# PCB_ExpansionModule_EXISTING_ERRORS.net
KiCad netlist of a schematic drawn in EasyEDA Pro
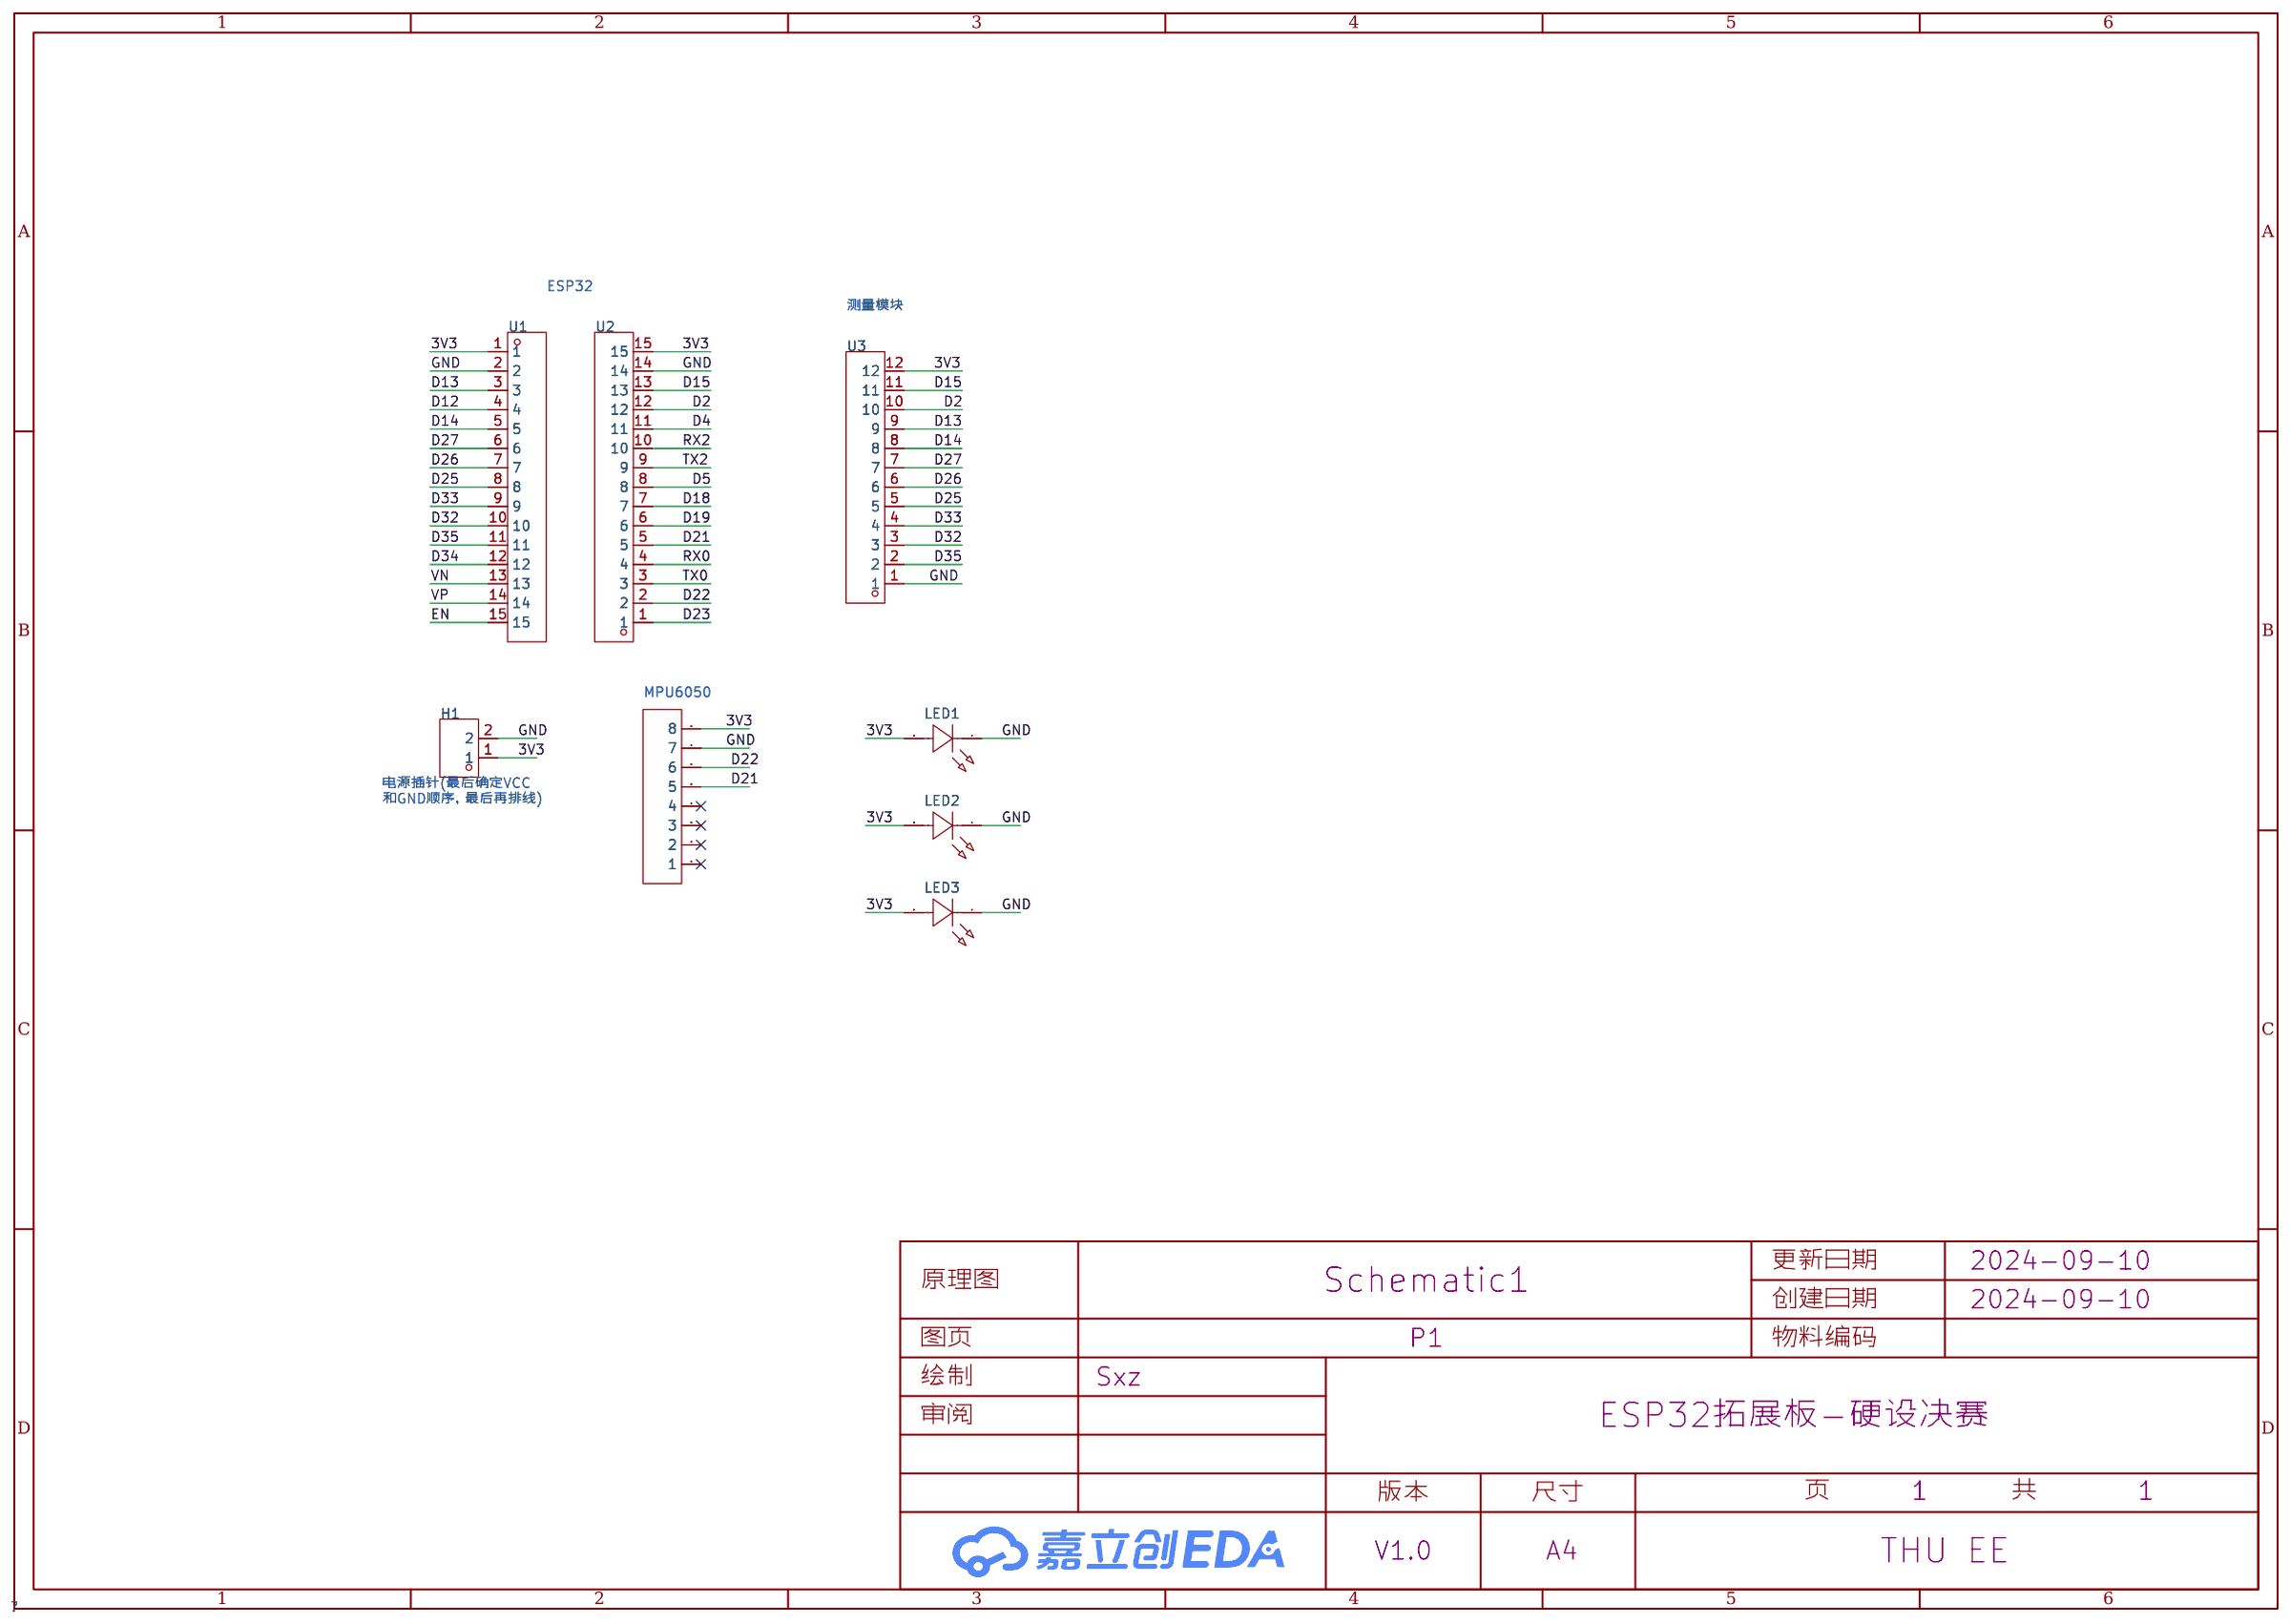
[diagram p0: schematic sheet]

(export (version "E")
  (design (tool "Eeschema 10.0.6"))
  (components
    (comp (ref "H1")
      (value "{制造商编号!}")
      (footprint "easyedapro:HDR-TH_2P-P2.54-H-M-W10.4")
      (fields (field (name "Manufacturer Part") "PZ254R-11-02P") (field (name "Manufacturer") "XFCN(兴飞)"))
      (libsource (lib "easyedapro") (part "PZ254R-11-02P"))
    )
    (comp (ref "LED1")
      (value "XL-1608SURC-06")
      (footprint "easyedapro:LED0603-RD_RED")
      (description "发光颜色:红色;功率:55mW;正向电流:25mA;主波长:617nm~621nm;透镜颜色:无色透明透镜;色温:-;发光角度:120°;载带方式:正贴;工作温度:-30°C~+85°C;")
      (fields (field (name "Manufacturer") "XINGLIGHT(成兴光)"))
      (libsource (lib "easyedapro") (part "XL-1608SURC-06"))
    )
    (comp (ref "LED2")
      (value "XL-1608SURC-06")
      (footprint "easyedapro:LED0603-RD_RED")
      (description "发光颜色:红色;功率:55mW;正向电流:25mA;主波长:617nm~621nm;透镜颜色:无色透明透镜;色温:-;发光角度:120°;载带方式:正贴;工作温度:-30°C~+85°C;")
      (fields (field (name "Manufacturer") "XINGLIGHT(成兴光)"))
      (libsource (lib "easyedapro") (part "XL-1608SURC-06"))
    )
    (comp (ref "LED3")
      (value "XL-1608SURC-06")
      (footprint "easyedapro:LED0603-RD_RED")
      (description "发光颜色:红色;功率:55mW;正向电流:25mA;主波长:617nm~621nm;透镜颜色:无色透明透镜;色温:-;发光角度:120°;载带方式:正贴;工作温度:-30°C~+85°C;")
      (fields (field (name "Manufacturer") "XINGLIGHT(成兴光)"))
      (libsource (lib "easyedapro") (part "XL-1608SURC-06"))
    )
    (comp (ref "P1")
      (value "2.54-1*8P母环保")
      (footprint "easyedapro:HDR-TH_8P-P2.54-V-F-1")
      (description "插孔结构:1x8P;间距:2.54mm;行距:-;安装类型:直插;排数:单排;总孔位数:8P;塑高:-;触头材质:-;触头镀层:-;")
      (fields (field (name "Manufacturer") "BOOMELE(博穆精密)"))
      (libsource (lib "easyedapro") (part "Header-Female-2.54_1x8"))
    )
    (comp (ref "U1")
      (value "KH-2.54FH-1X15P-H8.5")
      (footprint "easyedapro:HDR-TH_15P-P2.54-V-F")
      (fields (field (name "Manufacturer") "kinghelm(金航标)"))
      (libsource (lib "easyedapro") (part "KH-2.54FH-1X15P-H8.5"))
    )
    (comp (ref "U2")
      (value "KH-2.54FH-1X15P-H8.5")
      (footprint "easyedapro:HDR-TH_15P-P2.54-V-F")
      (fields (field (name "Manufacturer") "kinghelm(金航标)"))
      (libsource (lib "easyedapro") (part "KH-2.54FH-1X15P-H8.5"))
    )
    (comp (ref "U3")
      (value "KH-2.54FH-1X12P-H8.5")
      (footprint "easyedapro:HDR-TH_12P-P2.54-V-F")
      (fields (field (name "Manufacturer") "kinghelm(金航标)"))
      (libsource (lib "easyedapro") (part "KH-2.54FH-1X12P-H8.5"))
    )
  )
  (nets
    (net (code "1") (name "/3V3") (class "Default")
      (node (ref "H1") (pin "1") (pinfunction "1_1") (pintype "unspecified"))
      (node (ref "LED1") (pin "2") (pinfunction "A_2") (pintype "unspecified"))
      (node (ref "LED2") (pin "2") (pinfunction "A_2") (pintype "unspecified"))
      (node (ref "LED3") (pin "2") (pinfunction "A_2") (pintype "unspecified"))
      (node (ref "P1") (pin "8") (pinfunction "8_8") (pintype "input"))
      (node (ref "U1") (pin "1") (pinfunction "1_1") (pintype "unspecified"))
      (node (ref "U2") (pin "15") (pinfunction "15_15") (pintype "unspecified"))
      (node (ref "U3") (pin "12") (pinfunction "12_12") (pintype "unspecified"))
    )
    (net (code "2") (name "/D2") (class "Default")
      (node (ref "U2") (pin "12") (pinfunction "12_12") (pintype "unspecified"))
      (node (ref "U3") (pin "10") (pinfunction "10_10") (pintype "unspecified"))
    )
    (net (code "3") (name "/D4") (class "Default")
      (node (ref "U2") (pin "11") (pinfunction "11_11") (pintype "unspecified"))
    )
    (net (code "4") (name "/D5") (class "Default")
      (node (ref "U2") (pin "8") (pinfunction "8_8") (pintype "unspecified"))
    )
    (net (code "5") (name "/D12") (class "Default")
      (node (ref "U1") (pin "4") (pinfunction "4_4") (pintype "unspecified"))
    )
    (net (code "6") (name "/D13") (class "Default")
      (node (ref "U1") (pin "3") (pinfunction "3_3") (pintype "unspecified"))
      (node (ref "U3") (pin "9") (pinfunction "9_9") (pintype "unspecified"))
    )
    (net (code "7") (name "/D14") (class "Default")
      (node (ref "U1") (pin "5") (pinfunction "5_5") (pintype "unspecified"))
      (node (ref "U3") (pin "8") (pinfunction "8_8") (pintype "unspecified"))
    )
    (net (code "8") (name "/D15") (class "Default")
      (node (ref "U2") (pin "13") (pinfunction "13_13") (pintype "unspecified"))
      (node (ref "U3") (pin "11") (pinfunction "11_11") (pintype "unspecified"))
    )
    (net (code "9") (name "/D18") (class "Default")
      (node (ref "U2") (pin "7") (pinfunction "7_7") (pintype "unspecified"))
    )
    (net (code "10") (name "/D19") (class "Default")
      (node (ref "U2") (pin "6") (pinfunction "6_6") (pintype "unspecified"))
    )
    (net (code "11") (name "/D21") (class "Default")
      (node (ref "P1") (pin "5") (pinfunction "5_5") (pintype "input"))
      (node (ref "U2") (pin "5") (pinfunction "5_5") (pintype "unspecified"))
    )
    (net (code "12") (name "/D22") (class "Default")
      (node (ref "P1") (pin "6") (pinfunction "6_6") (pintype "input"))
      (node (ref "U2") (pin "2") (pinfunction "2_2") (pintype "unspecified"))
    )
    (net (code "13") (name "/D23") (class "Default")
      (node (ref "U2") (pin "1") (pinfunction "1_1") (pintype "unspecified"))
    )
    (net (code "14") (name "/D25") (class "Default")
      (node (ref "U1") (pin "8") (pinfunction "8_8") (pintype "unspecified"))
      (node (ref "U3") (pin "5") (pinfunction "5_5") (pintype "unspecified"))
    )
    (net (code "15") (name "/D26") (class "Default")
      (node (ref "U1") (pin "7") (pinfunction "7_7") (pintype "unspecified"))
      (node (ref "U3") (pin "6") (pinfunction "6_6") (pintype "unspecified"))
    )
    (net (code "16") (name "/D27") (class "Default")
      (node (ref "U1") (pin "6") (pinfunction "6_6") (pintype "unspecified"))
      (node (ref "U3") (pin "7") (pinfunction "7_7") (pintype "unspecified"))
    )
    (net (code "17") (name "/D32") (class "Default")
      (node (ref "U1") (pin "10") (pinfunction "10_10") (pintype "unspecified"))
      (node (ref "U3") (pin "3") (pinfunction "3_3") (pintype "unspecified"))
    )
    (net (code "18") (name "/D33") (class "Default")
      (node (ref "U1") (pin "9") (pinfunction "9_9") (pintype "unspecified"))
      (node (ref "U3") (pin "4") (pinfunction "4_4") (pintype "unspecified"))
    )
    (net (code "19") (name "/D34") (class "Default")
      (node (ref "U1") (pin "12") (pinfunction "12_12") (pintype "unspecified"))
    )
    (net (code "20") (name "/D35") (class "Default")
      (node (ref "U1") (pin "11") (pinfunction "11_11") (pintype "unspecified"))
      (node (ref "U3") (pin "2") (pinfunction "2_2") (pintype "unspecified"))
    )
    (net (code "21") (name "/EN") (class "Default")
      (node (ref "U1") (pin "15") (pinfunction "15_15") (pintype "unspecified"))
    )
    (net (code "22") (name "/GND") (class "Default")
      (node (ref "H1") (pin "2") (pinfunction "2_2") (pintype "unspecified"))
      (node (ref "LED1") (pin "1") (pinfunction "K_1") (pintype "unspecified"))
      (node (ref "LED2") (pin "1") (pinfunction "K_1") (pintype "unspecified"))
      (node (ref "LED3") (pin "1") (pinfunction "K_1") (pintype "unspecified"))
      (node (ref "P1") (pin "7") (pinfunction "7_7") (pintype "input"))
      (node (ref "U1") (pin "2") (pinfunction "2_2") (pintype "unspecified"))
      (node (ref "U2") (pin "14") (pinfunction "14_14") (pintype "unspecified"))
      (node (ref "U3") (pin "1") (pinfunction "1_1") (pintype "unspecified"))
    )
    (net (code "23") (name "/RX0") (class "Default")
      (node (ref "U2") (pin "4") (pinfunction "4_4") (pintype "unspecified"))
    )
    (net (code "24") (name "/RX2") (class "Default")
      (node (ref "U2") (pin "10") (pinfunction "10_10") (pintype "unspecified"))
    )
    (net (code "25") (name "/TX0") (class "Default")
      (node (ref "U2") (pin "3") (pinfunction "3_3") (pintype "unspecified"))
    )
    (net (code "26") (name "/TX2") (class "Default")
      (node (ref "U2") (pin "9") (pinfunction "9_9") (pintype "unspecified"))
    )
    (net (code "27") (name "/VN") (class "Default")
      (node (ref "U1") (pin "13") (pinfunction "13_13") (pintype "unspecified"))
    )
    (net (code "28") (name "/VP") (class "Default")
      (node (ref "U1") (pin "14") (pinfunction "14_14") (pintype "unspecified"))
    )
    (net (code "29") (name "unconnected-(P1-Pad1)") (class "Default")
      (node (ref "P1") (pin "1") (pinfunction "1_1") (pintype "input+no_connect"))
    )
    (net (code "30") (name "unconnected-(P1-Pad2)") (class "Default")
      (node (ref "P1") (pin "2") (pinfunction "2_2") (pintype "input+no_connect"))
    )
    (net (code "31") (name "unconnected-(P1-Pad3)") (class "Default")
      (node (ref "P1") (pin "3") (pinfunction "3_3") (pintype "input+no_connect"))
    )
    (net (code "32") (name "unconnected-(P1-Pad4)") (class "Default")
      (node (ref "P1") (pin "4") (pinfunction "4_4") (pintype "input+no_connect"))
    )
  )
)
